# B293A_Connectors.net
KiCad netlist of a schematic drawn in Altium Designer
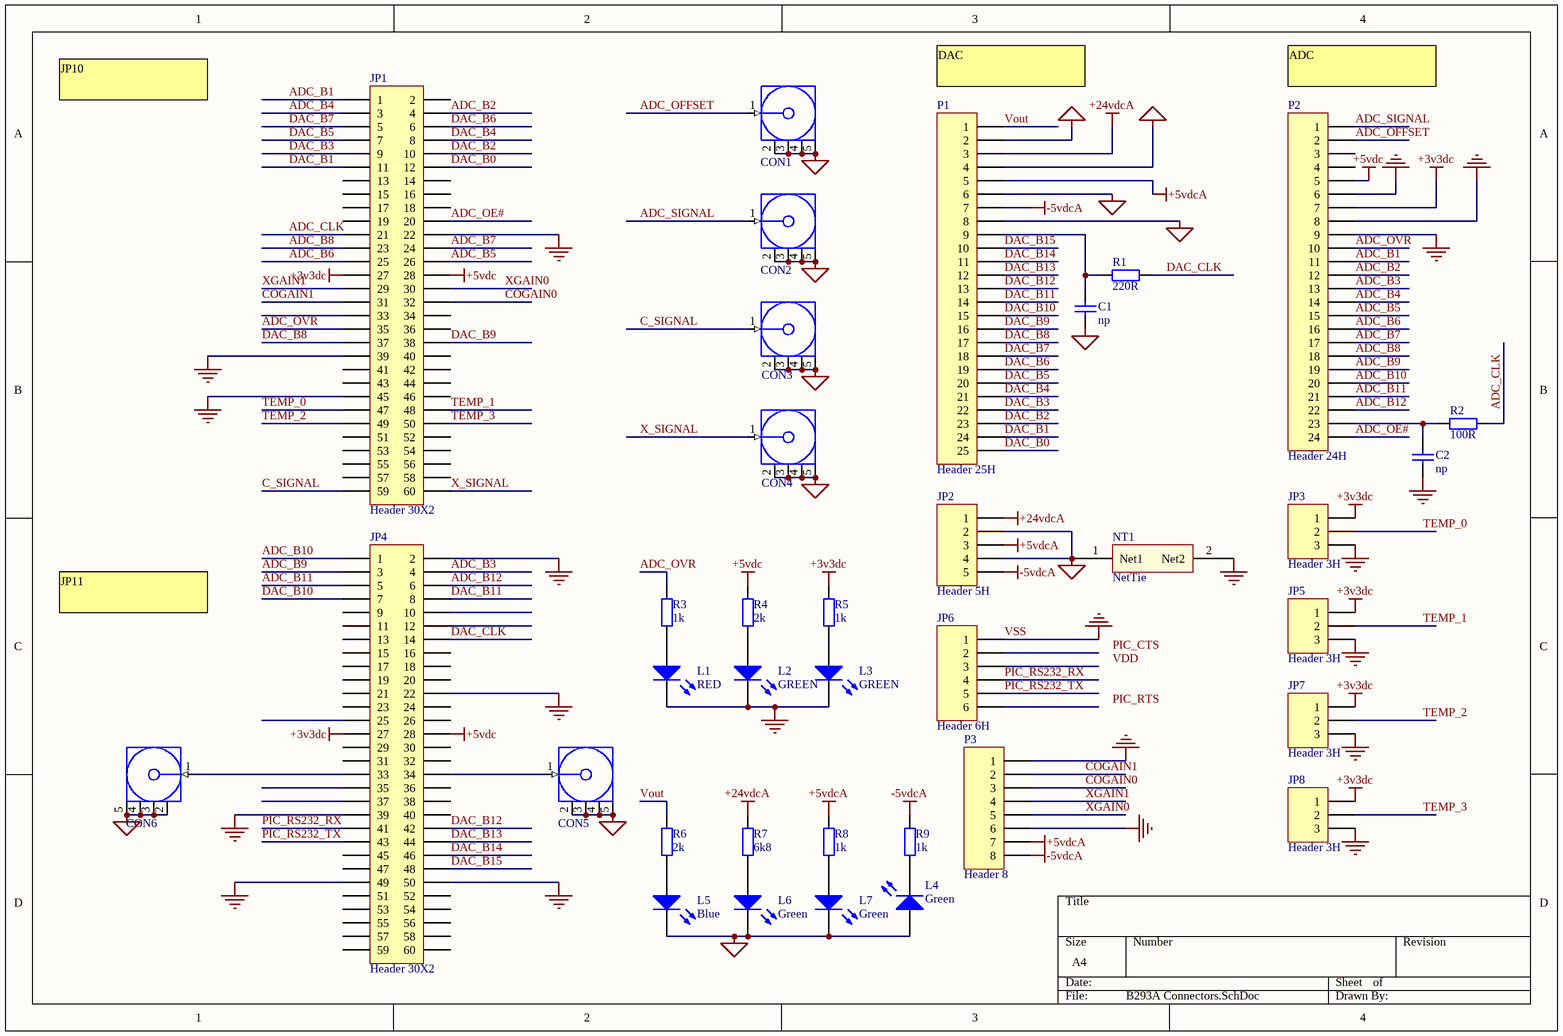
[diagram p0: B293A Connectors.SchDoc]

(export (version "E")
  (design (tool "Eeschema 10.0.6"))
  (components
    (comp (ref "C1")
      (value "np")
      (footprint "1206")
      (description "Capacitor")
      (libsource (lib "Matt SCH Library") (part "CAP"))
    )
    (comp (ref "C2")
      (value "np")
      (footprint "1206")
      (description "Capacitor")
      (libsource (lib "Matt SCH Library") (part "CAP"))
    )
    (comp (ref "CON1")
      (value "SMA Vertical")
      (footprint "Matt PCB Library:SMA Vertical")
      (fields (field (name "MANUFACTURERS PART NO") "5-1814832-1"))
      (libsource (lib "Matt SCH Library") (part "SMA Vertical"))
    )
    (comp (ref "CON2")
      (value "SMA Vertical")
      (footprint "Matt PCB Library:SMA Vertical")
      (fields (field (name "MANUFACTURERS PART NO") "5-1814832-1"))
      (libsource (lib "Matt SCH Library") (part "SMA Vertical"))
    )
    (comp (ref "CON3")
      (value "SMA Vertical")
      (footprint "Matt PCB Library:SMA Vertical")
      (fields (field (name "MANUFACTURERS PART NO") "5-1814832-1"))
      (libsource (lib "Matt SCH Library") (part "SMA Vertical"))
    )
    (comp (ref "CON4")
      (value "SMA Vertical")
      (footprint "Matt PCB Library:SMA Vertical")
      (fields (field (name "MANUFACTURERS PART NO") "5-1814832-1"))
      (libsource (lib "Matt SCH Library") (part "SMA Vertical"))
    )
    (comp (ref "CON5")
      (value "SMA Vertical")
      (footprint "Matt PCB Library:SMA Vertical")
      (fields (field (name "MANUFACTURERS PART NO") "5-1814832-1"))
      (libsource (lib "Matt SCH Library") (part "SMA Vertical"))
    )
    (comp (ref "CON6")
      (value "SMA Vertical")
      (footprint "Matt PCB Library:SMA Vertical")
      (fields (field (name "MANUFACTURERS PART NO") "5-1814832-1"))
      (libsource (lib "Matt SCH Library") (part "SMA Vertical"))
    )
    (comp (ref "JP1")
      (value "Header 30X2")
      (footprint "HDR2X30")
      (description "Header, 30-Pin, Dual row")
      (fields (field (name "PUBLISHER") "Altium Limited"))
      (libsource (lib "Miscellaneous Connectors") (part "Header 30X2"))
    )
    (comp (ref "JP2")
      (value "Header 5H")
      (footprint "HDR1X5H")
      (description "Header, 5-Pin, Right Angle")
      (fields
        (field (name "MANUFACTURER PART NUMBER") "70543-0007")
        (field (name "PUBLISHER") "Altium Limited")
      )
      (libsource (lib "Miscellaneous Connectors") (part "Header 5H"))
    )
    (comp (ref "JP3")
      (value "Header 3H")
      (footprint "HDR1X3H")
      (description "Header, 3-Pin, Right Angle")
      (fields
        (field (name "MANUFACTURER PART NUMBER") "70553-0002")
        (field (name "PUBLISHER") "Altium Limited")
      )
      (libsource (lib "Miscellaneous Connectors") (part "Header 3H"))
    )
    (comp (ref "JP4")
      (value "Header 30X2")
      (footprint "HDR2X30")
      (description "Header, 30-Pin, Dual row")
      (fields (field (name "PUBLISHER") "Altium Limited"))
      (libsource (lib "Miscellaneous Connectors") (part "Header 30X2"))
    )
    (comp (ref "JP5")
      (value "Header 3H")
      (footprint "HDR1X3H")
      (description "Header, 3-Pin, Right Angle")
      (fields (field (name "PUBLISHER") "Altium Limited"))
      (libsource (lib "Miscellaneous Connectors") (part "Header 3H"))
    )
    (comp (ref "JP6")
      (value "Header 6H")
      (footprint "HDR1X6H")
      (description "Header, 6-Pin, Right Angle")
      (fields (field (name "PUBLISHER") "Altium Limited"))
      (libsource (lib "Miscellaneous Connectors") (part "Header 6H"))
    )
    (comp (ref "JP7")
      (value "Header 3H")
      (footprint "HDR1X3H")
      (description "Header, 3-Pin, Right Angle")
      (fields (field (name "PUBLISHER") "Altium Limited"))
      (libsource (lib "Miscellaneous Connectors") (part "Header 3H"))
    )
    (comp (ref "JP8")
      (value "Header 3H")
      (footprint "HDR1X3H")
      (description "Header, 3-Pin, Right Angle")
      (fields (field (name "PUBLISHER") "Altium Limited"))
      (libsource (lib "Miscellaneous Connectors") (part "Header 3H"))
    )
    (comp (ref "L1")
      (value "RED")
      (footprint "Matt PCB Library:1206 - LED")
      (libsource (lib "Matt SCH Library") (part "LED 1206"))
    )
    (comp (ref "L2")
      (value "GREEN")
      (footprint "Matt PCB Library:1206 - LED")
      (libsource (lib "Matt SCH Library") (part "LED 1206"))
    )
    (comp (ref "L3")
      (value "GREEN")
      (footprint "Matt PCB Library:1206 - LED")
      (libsource (lib "Matt SCH Library") (part "LED 1206"))
    )
    (comp (ref "L4")
      (value "Green")
      (footprint "Matt PCB Library:1206 - LED")
      (libsource (lib "Matt SCH Library") (part "LED 1206"))
    )
    (comp (ref "L5")
      (value "Blue")
      (footprint "Matt PCB Library:1206 - LED")
      (libsource (lib "Matt SCH Library") (part "LED 1206"))
    )
    (comp (ref "L6")
      (value "Green")
      (footprint "Matt PCB Library:1206 - LED")
      (libsource (lib "Matt SCH Library") (part "LED 1206"))
    )
    (comp (ref "L7")
      (value "Green")
      (footprint "Matt PCB Library:1206 - LED")
      (libsource (lib "Matt SCH Library") (part "LED 1206"))
    )
    (comp (ref "NT1")
      (value "NetTie")
      (footprint "NetTie")
      (libsource (lib "Matt SCH Library") (part "NetTie"))
    )
    (comp (ref "P1")
      (value "Header 25H")
      (footprint "HDR1X25H")
      (description "Header, 25-Pin, Right Angle")
      (fields (field (name "PUBLISHER") "Altium Limited"))
      (libsource (lib "Miscellaneous Connectors") (part "Header 25H"))
    )
    (comp (ref "P2")
      (value "Header 24H")
      (footprint "HDR1X24H")
      (description "Header, 24-Pin, Right Angle")
      (fields (field (name "PUBLISHER") "Altium Limited"))
      (libsource (lib "Miscellaneous Connectors") (part "Header 24H"))
    )
    (comp (ref "P3")
      (value "Header 8")
      (footprint "HDR1X8")
      (description "Header, 8-Pin")
      (fields
        (field (name "MAANUFACTURER PART NUMBER") "70543-0007")
        (field (name "PUBLISHER") "Altium Limited")
      )
      (libsource (lib "Miscellaneous Connectors") (part "Header 8"))
    )
    (comp (ref "R1") (value "220R") (footprint "1206") (libsource (lib "") (part "RES2_1")))
    (comp (ref "R2") (value "100R") (footprint "1206") (libsource (lib "") (part "RES2_1")))
    (comp (ref "R3") (value "1k") (footprint "1206") (libsource (lib "Matt SCH Library") (part "RES2")))
    (comp (ref "R4") (value "2k") (footprint "1206") (libsource (lib "Matt SCH Library") (part "RES2")))
    (comp (ref "R5") (value "1k") (footprint "1206") (libsource (lib "Matt SCH Library") (part "RES2")))
    (comp (ref "R6") (value "2k") (footprint "1206") (libsource (lib "Matt SCH Library") (part "RES2")))
    (comp (ref "R7") (value "6k8") (footprint "1206") (libsource (lib "Matt SCH Library") (part "RES2")))
    (comp (ref "R8") (value "1k") (footprint "1206") (libsource (lib "Matt SCH Library") (part "RES2")))
    (comp (ref "R9") (value "1k") (footprint "1206") (libsource (lib "") (part "RES2_2")))
  )
  (nets
    (net (code "1") (name "+3v3dc") (class "Default")
      (node (ref "JP1") (pin "27") (pinfunction "27_27") (pintype "passive"))
      (node (ref "JP3") (pin "1") (pinfunction "1_1") (pintype "passive"))
      (node (ref "JP4") (pin "27") (pinfunction "27_27") (pintype "passive"))
      (node (ref "JP5") (pin "1") (pinfunction "1_1") (pintype "passive"))
      (node (ref "JP7") (pin "1") (pinfunction "1_1") (pintype "passive"))
      (node (ref "JP8") (pin "1") (pinfunction "1_1") (pintype "passive"))
      (node (ref "P2") (pin "7") (pinfunction "7_7") (pintype "passive"))
      (node (ref "R5") (pin "2") (pinfunction "2_2") (pintype "passive"))
    )
    (net (code "2") (name "+5vdc") (class "Default")
      (node (ref "JP1") (pin "28") (pinfunction "28_28") (pintype "passive"))
      (node (ref "JP4") (pin "28") (pinfunction "28_28") (pintype "passive"))
      (node (ref "P2") (pin "5") (pinfunction "5_5") (pintype "passive"))
      (node (ref "R4") (pin "2") (pinfunction "2_2") (pintype "passive"))
    )
    (net (code "3") (name "+5vdcA") (class "Default")
      (node (ref "JP2") (pin "3") (pinfunction "3_3") (pintype "passive"))
      (node (ref "P1") (pin "5") (pinfunction "5_5") (pintype "passive"))
      (node (ref "P3") (pin "7") (pinfunction "7_7") (pintype "passive"))
      (node (ref "R8") (pin "2") (pinfunction "2_2") (pintype "passive"))
    )
    (net (code "4") (name "+24vdcA") (class "Default")
      (node (ref "JP2") (pin "1") (pinfunction "1_1") (pintype "passive"))
      (node (ref "P1") (pin "3") (pinfunction "3_3") (pintype "passive"))
      (node (ref "R7") (pin "2") (pinfunction "2_2") (pintype "passive"))
    )
    (net (code "5") (name "-5vdcA") (class "Default")
      (node (ref "JP2") (pin "5") (pinfunction "5_5") (pintype "passive"))
      (node (ref "P1") (pin "7") (pinfunction "7_7") (pintype "passive"))
      (node (ref "P3") (pin "8") (pinfunction "8_8") (pintype "passive"))
      (node (ref "R9") (pin "1") (pinfunction "1_1") (pintype "passive"))
    )
    (net (code "6") (name "/ADC_B1") (class "Default")
      (node (ref "JP1") (pin "1") (pinfunction "1_1") (pintype "passive"))
      (node (ref "P2") (pin "11") (pinfunction "11_11") (pintype "passive"))
    )
    (net (code "7") (name "/ADC_B2") (class "Default")
      (node (ref "JP1") (pin "4") (pinfunction "4_4") (pintype "passive"))
      (node (ref "P2") (pin "12") (pinfunction "12_12") (pintype "passive"))
    )
    (net (code "8") (name "/ADC_B3") (class "Default")
      (node (ref "JP4") (pin "4") (pinfunction "4_4") (pintype "passive"))
      (node (ref "P2") (pin "13") (pinfunction "13_13") (pintype "passive"))
    )
    (net (code "9") (name "/ADC_B4") (class "Default")
      (node (ref "JP1") (pin "3") (pinfunction "3_3") (pintype "passive"))
      (node (ref "P2") (pin "14") (pinfunction "14_14") (pintype "passive"))
    )
    (net (code "10") (name "/ADC_B5") (class "Default")
      (node (ref "JP1") (pin "26") (pinfunction "26_26") (pintype "passive"))
      (node (ref "P2") (pin "15") (pinfunction "15_15") (pintype "passive"))
    )
    (net (code "11") (name "/ADC_B6") (class "Default")
      (node (ref "JP1") (pin "25") (pinfunction "25_25") (pintype "passive"))
      (node (ref "P2") (pin "16") (pinfunction "16_16") (pintype "passive"))
    )
    (net (code "12") (name "/ADC_B7") (class "Default")
      (node (ref "JP1") (pin "24") (pinfunction "24_24") (pintype "passive"))
      (node (ref "P2") (pin "17") (pinfunction "17_17") (pintype "passive"))
    )
    (net (code "13") (name "/ADC_B8") (class "Default")
      (node (ref "JP1") (pin "23") (pinfunction "23_23") (pintype "passive"))
      (node (ref "P2") (pin "18") (pinfunction "18_18") (pintype "passive"))
    )
    (net (code "14") (name "/ADC_B9") (class "Default")
      (node (ref "JP4") (pin "3") (pinfunction "3_3") (pintype "passive"))
      (node (ref "P2") (pin "19") (pinfunction "19_19") (pintype "passive"))
    )
    (net (code "15") (name "/ADC_B10") (class "Default")
      (node (ref "JP4") (pin "1") (pinfunction "1_1") (pintype "passive"))
      (node (ref "P2") (pin "20") (pinfunction "20_20") (pintype "passive"))
    )
    (net (code "16") (name "/ADC_B11") (class "Default")
      (node (ref "JP4") (pin "5") (pinfunction "5_5") (pintype "passive"))
      (node (ref "P2") (pin "21") (pinfunction "21_21") (pintype "passive"))
    )
    (net (code "17") (name "/ADC_B12") (class "Default")
      (node (ref "JP4") (pin "6") (pinfunction "6_6") (pintype "passive"))
      (node (ref "P2") (pin "22") (pinfunction "22_22") (pintype "passive"))
    )
    (net (code "18") (name "/ADC_CLK") (class "Default")
      (node (ref "JP1") (pin "21") (pinfunction "21_21") (pintype "passive"))
      (node (ref "R2") (pin "2") (pinfunction "2_2") (pintype "passive"))
    )
    (net (code "19") (name "/ADC_OE#") (class "Default")
      (node (ref "JP1") (pin "20") (pinfunction "20_20") (pintype "passive"))
      (node (ref "P2") (pin "24") (pinfunction "24_24") (pintype "passive"))
    )
    (net (code "20") (name "/ADC_OFFSET") (class "Default")
      (node (ref "CON1") (pin "1") (pinfunction "Signal_1") (pintype "input"))
      (node (ref "P2") (pin "2") (pinfunction "2_2") (pintype "passive"))
    )
    (net (code "21") (name "/ADC_OVR") (class "Default")
      (node (ref "JP1") (pin "35") (pinfunction "35_35") (pintype "passive"))
      (node (ref "P2") (pin "10") (pinfunction "10_10") (pintype "passive"))
      (node (ref "R3") (pin "2") (pinfunction "2_2") (pintype "passive"))
    )
    (net (code "22") (name "/ADC_SIGNAL") (class "Default")
      (node (ref "CON2") (pin "1") (pinfunction "Signal_1") (pintype "input"))
      (node (ref "P2") (pin "1") (pinfunction "1_1") (pintype "passive"))
    )
    (net (code "23") (name "/COGAIN0") (class "Default")
      (node (ref "JP1") (pin "32") (pinfunction "32_32") (pintype "passive"))
      (node (ref "P3") (pin "3") (pinfunction "3_3") (pintype "passive"))
    )
    (net (code "24") (name "/COGAIN1") (class "Default")
      (node (ref "JP1") (pin "31") (pinfunction "31_31") (pintype "passive"))
      (node (ref "P3") (pin "2") (pinfunction "2_2") (pintype "passive"))
    )
    (net (code "25") (name "/C_SIGNAL") (class "Default")
      (node (ref "CON3") (pin "1") (pinfunction "Signal_1") (pintype "input"))
      (node (ref "JP1") (pin "59") (pinfunction "59_59") (pintype "passive"))
    )
    (net (code "26") (name "/DAC_B0") (class "Default")
      (node (ref "JP1") (pin "12") (pinfunction "12_12") (pintype "passive"))
      (node (ref "P1") (pin "25") (pinfunction "25_25") (pintype "passive"))
    )
    (net (code "27") (name "/DAC_B1") (class "Default")
      (node (ref "JP1") (pin "11") (pinfunction "11_11") (pintype "passive"))
      (node (ref "P1") (pin "24") (pinfunction "24_24") (pintype "passive"))
    )
    (net (code "28") (name "/DAC_B2") (class "Default")
      (node (ref "JP1") (pin "10") (pinfunction "10_10") (pintype "passive"))
      (node (ref "P1") (pin "23") (pinfunction "23_23") (pintype "passive"))
    )
    (net (code "29") (name "/DAC_B3") (class "Default")
      (node (ref "JP1") (pin "9") (pinfunction "9_9") (pintype "passive"))
      (node (ref "P1") (pin "22") (pinfunction "22_22") (pintype "passive"))
    )
    (net (code "30") (name "/DAC_B4") (class "Default")
      (node (ref "JP1") (pin "8") (pinfunction "8_8") (pintype "passive"))
      (node (ref "P1") (pin "21") (pinfunction "21_21") (pintype "passive"))
    )
    (net (code "31") (name "/DAC_B5") (class "Default")
      (node (ref "JP1") (pin "7") (pinfunction "7_7") (pintype "passive"))
      (node (ref "P1") (pin "20") (pinfunction "20_20") (pintype "passive"))
    )
    (net (code "32") (name "/DAC_B6") (class "Default")
      (node (ref "JP1") (pin "6") (pinfunction "6_6") (pintype "passive"))
      (node (ref "P1") (pin "19") (pinfunction "19_19") (pintype "passive"))
    )
    (net (code "33") (name "/DAC_B7") (class "Default")
      (node (ref "JP1") (pin "5") (pinfunction "5_5") (pintype "passive"))
      (node (ref "P1") (pin "18") (pinfunction "18_18") (pintype "passive"))
    )
    (net (code "34") (name "/DAC_B8") (class "Default")
      (node (ref "JP1") (pin "37") (pinfunction "37_37") (pintype "passive"))
      (node (ref "P1") (pin "17") (pinfunction "17_17") (pintype "passive"))
    )
    (net (code "35") (name "/DAC_B9") (class "Default")
      (node (ref "JP1") (pin "38") (pinfunction "38_38") (pintype "passive"))
      (node (ref "P1") (pin "16") (pinfunction "16_16") (pintype "passive"))
    )
    (net (code "36") (name "/DAC_B10") (class "Default")
      (node (ref "JP4") (pin "7") (pinfunction "7_7") (pintype "passive"))
      (node (ref "P1") (pin "15") (pinfunction "15_15") (pintype "passive"))
    )
    (net (code "37") (name "/DAC_B11") (class "Default")
      (node (ref "JP4") (pin "8") (pinfunction "8_8") (pintype "passive"))
      (node (ref "P1") (pin "14") (pinfunction "14_14") (pintype "passive"))
    )
    (net (code "38") (name "/DAC_B12") (class "Default")
      (node (ref "JP4") (pin "42") (pinfunction "42_42") (pintype "passive"))
      (node (ref "P1") (pin "13") (pinfunction "13_13") (pintype "passive"))
    )
    (net (code "39") (name "/DAC_B13") (class "Default")
      (node (ref "JP4") (pin "44") (pinfunction "44_44") (pintype "passive"))
      (node (ref "P1") (pin "12") (pinfunction "12_12") (pintype "passive"))
    )
    (net (code "40") (name "/DAC_B14") (class "Default")
      (node (ref "JP4") (pin "46") (pinfunction "46_46") (pintype "passive"))
      (node (ref "P1") (pin "11") (pinfunction "11_11") (pintype "passive"))
    )
    (net (code "41") (name "/DAC_B15") (class "Default")
      (node (ref "JP4") (pin "48") (pinfunction "48_48") (pintype "passive"))
      (node (ref "P1") (pin "10") (pinfunction "10_10") (pintype "passive"))
    )
    (net (code "42") (name "/DAC_CLK") (class "Default")
      (node (ref "JP4") (pin "14") (pinfunction "14_14") (pintype "passive"))
      (node (ref "R1") (pin "2") (pinfunction "2_2") (pintype "passive"))
    )
    (net (code "44") (name "/PIC_RS232_RX") (class "Default")
      (node (ref "JP4") (pin "41") (pinfunction "41_41") (pintype "passive"))
      (node (ref "JP6") (pin "4") (pinfunction "4_4") (pintype "passive"))
    )
    (net (code "45") (name "/PIC_RS232_TX") (class "Default")
      (node (ref "JP4") (pin "43") (pinfunction "43_43") (pintype "passive"))
      (node (ref "JP6") (pin "5") (pinfunction "5_5") (pintype "passive"))
    )
    (net (code "47") (name "/TEMP_0") (class "Default")
      (node (ref "JP1") (pin "47") (pinfunction "47_47") (pintype "passive"))
      (node (ref "JP3") (pin "2") (pinfunction "2_2") (pintype "passive"))
    )
    (net (code "48") (name "/TEMP_1") (class "Default")
      (node (ref "JP1") (pin "48") (pinfunction "48_48") (pintype "passive"))
      (node (ref "JP5") (pin "2") (pinfunction "2_2") (pintype "passive"))
    )
    (net (code "49") (name "/TEMP_2") (class "Default")
      (node (ref "JP1") (pin "49") (pinfunction "49_49") (pintype "passive"))
      (node (ref "JP7") (pin "2") (pinfunction "2_2") (pintype "passive"))
    )
    (net (code "50") (name "/TEMP_3") (class "Default")
      (node (ref "JP1") (pin "50") (pinfunction "50_50") (pintype "passive"))
      (node (ref "JP8") (pin "2") (pinfunction "2_2") (pintype "passive"))
    )
    (net (code "52") (name "/Vout") (class "Default")
      (node (ref "P1") (pin "1") (pinfunction "1_1") (pintype "passive"))
      (node (ref "R6") (pin "2") (pinfunction "2_2") (pintype "passive"))
    )
    (net (code "53") (name "/XGAIN0") (class "Default")
      (node (ref "JP1") (pin "30") (pinfunction "30_30") (pintype "passive"))
      (node (ref "P3") (pin "5") (pinfunction "5_5") (pintype "passive"))
    )
    (net (code "54") (name "/XGAIN1") (class "Default")
      (node (ref "JP1") (pin "29") (pinfunction "29_29") (pintype "passive"))
      (node (ref "P3") (pin "4") (pinfunction "4_4") (pintype "passive"))
    )
    (net (code "55") (name "/X_SIGNAL") (class "Default")
      (node (ref "CON4") (pin "1") (pinfunction "Signal_1") (pintype "input"))
      (node (ref "JP1") (pin "60") (pinfunction "60_60") (pintype "passive"))
    )
    (net (code "56") (name "AGND") (class "Default")
      (node (ref "C1") (pin "2") (pinfunction "2_2") (pintype "passive"))
      (node (ref "CON1") (pin "2") (pinfunction "GND_2") (pintype "power_in"))
      (node (ref "CON1") (pin "3") (pinfunction "GND_3") (pintype "power_in"))
      (node (ref "CON1") (pin "4") (pinfunction "GND_4") (pintype "power_in"))
      (node (ref "CON1") (pin "5") (pinfunction "GND_5") (pintype "power_in"))
      (node (ref "CON2") (pin "2") (pinfunction "GND_2") (pintype "power_in"))
      (node (ref "CON2") (pin "3") (pinfunction "GND_3") (pintype "power_in"))
      (node (ref "CON2") (pin "4") (pinfunction "GND_4") (pintype "power_in"))
      (node (ref "CON2") (pin "5") (pinfunction "GND_5") (pintype "power_in"))
      (node (ref "CON3") (pin "2") (pinfunction "GND_2") (pintype "power_in"))
      (node (ref "CON3") (pin "3") (pinfunction "GND_3") (pintype "power_in"))
      (node (ref "CON3") (pin "4") (pinfunction "GND_4") (pintype "power_in"))
      (node (ref "CON3") (pin "5") (pinfunction "GND_5") (pintype "power_in"))
      (node (ref "CON4") (pin "2") (pinfunction "GND_2") (pintype "power_in"))
      (node (ref "CON4") (pin "3") (pinfunction "GND_3") (pintype "power_in"))
      (node (ref "CON4") (pin "4") (pinfunction "GND_4") (pintype "power_in"))
      (node (ref "CON4") (pin "5") (pinfunction "GND_5") (pintype "power_in"))
      (node (ref "CON5") (pin "2") (pinfunction "GND_2") (pintype "power_in"))
      (node (ref "CON5") (pin "3") (pinfunction "GND_3") (pintype "power_in"))
      (node (ref "CON5") (pin "4") (pinfunction "GND_4") (pintype "power_in"))
      (node (ref "CON5") (pin "5") (pinfunction "GND_5") (pintype "power_in"))
      (node (ref "CON6") (pin "2") (pinfunction "GND_2") (pintype "power_in"))
      (node (ref "CON6") (pin "3") (pinfunction "GND_3") (pintype "power_in"))
      (node (ref "CON6") (pin "4") (pinfunction "GND_4") (pintype "power_in"))
      (node (ref "CON6") (pin "5") (pinfunction "GND_5") (pintype "power_in"))
      (node (ref "JP2") (pin "2") (pinfunction "2_2") (pintype "passive"))
      (node (ref "JP2") (pin "4") (pinfunction "4_4") (pintype "passive"))
      (node (ref "L4") (pin "A") (pinfunction "A_A") (pintype "passive"))
      (node (ref "L5") (pin "K") (pinfunction "K_K") (pintype "passive"))
      (node (ref "L6") (pin "K") (pinfunction "K_K") (pintype "passive"))
      (node (ref "L7") (pin "K") (pinfunction "K_K") (pintype "passive"))
      (node (ref "NT1") (pin "1") (pinfunction "Net1_1") (pintype "passive"))
      (node (ref "P1") (pin "2") (pinfunction "2_2") (pintype "passive"))
      (node (ref "P1") (pin "4") (pinfunction "4_4") (pintype "passive"))
      (node (ref "P1") (pin "6") (pinfunction "6_6") (pintype "passive"))
      (node (ref "P1") (pin "8") (pinfunction "8_8") (pintype "passive"))
    )
    (net (code "57") (name "GND") (class "Default")
      (node (ref "C2") (pin "2") (pinfunction "2_2") (pintype "passive"))
      (node (ref "JP1") (pin "22") (pinfunction "22_22") (pintype "passive"))
      (node (ref "JP1") (pin "39") (pinfunction "39_39") (pintype "passive"))
      (node (ref "JP1") (pin "45") (pinfunction "45_45") (pintype "passive"))
      (node (ref "JP3") (pin "3") (pinfunction "3_3") (pintype "passive"))
      (node (ref "JP4") (pin "2") (pinfunction "2_2") (pintype "passive"))
      (node (ref "JP4") (pin "22") (pinfunction "22_22") (pintype "passive"))
      (node (ref "JP4") (pin "39") (pinfunction "39_39") (pintype "passive"))
      (node (ref "JP4") (pin "49") (pinfunction "49_49") (pintype "passive"))
      (node (ref "JP4") (pin "50") (pinfunction "50_50") (pintype "passive"))
      (node (ref "JP5") (pin "3") (pinfunction "3_3") (pintype "passive"))
      (node (ref "JP6") (pin "1") (pinfunction "1_1") (pintype "passive"))
      (node (ref "JP7") (pin "3") (pinfunction "3_3") (pintype "passive"))
      (node (ref "JP8") (pin "3") (pinfunction "3_3") (pintype "passive"))
      (node (ref "L1") (pin "K") (pinfunction "K_K") (pintype "passive"))
      (node (ref "L2") (pin "K") (pinfunction "K_K") (pintype "passive"))
      (node (ref "L3") (pin "K") (pinfunction "K_K") (pintype "passive"))
      (node (ref "NT1") (pin "2") (pinfunction "Net2_2") (pintype "passive"))
      (node (ref "P2") (pin "6") (pinfunction "6_6") (pintype "passive"))
      (node (ref "P2") (pin "8") (pinfunction "8_8") (pintype "passive"))
      (node (ref "P2") (pin "9") (pinfunction "9_9") (pintype "passive"))
      (node (ref "P3") (pin "1") (pinfunction "1_1") (pintype "passive"))
      (node (ref "P3") (pin "6") (pinfunction "6_6") (pintype "passive"))
    )
    (net (code "58") (name "Net-(C1-Pad1)") (class "Default")
      (node (ref "C1") (pin "1") (pinfunction "1_1") (pintype "passive"))
      (node (ref "P1") (pin "9") (pinfunction "9_9") (pintype "passive"))
      (node (ref "R1") (pin "1") (pinfunction "1_1") (pintype "passive"))
    )
    (net (code "59") (name "Net-(C2-Pad1)") (class "Default")
      (node (ref "C2") (pin "1") (pinfunction "1_1") (pintype "passive"))
      (node (ref "P2") (pin "23") (pinfunction "23_23") (pintype "passive"))
      (node (ref "R2") (pin "1") (pinfunction "1_1") (pintype "passive"))
    )
    (net (code "60") (name "Net-(CON5-Signal)") (class "Default")
      (node (ref "CON5") (pin "1") (pinfunction "Signal_1") (pintype "input"))
      (node (ref "JP4") (pin "34") (pinfunction "34_34") (pintype "passive"))
    )
    (net (code "61") (name "Net-(CON6-Signal)") (class "Default")
      (node (ref "CON6") (pin "1") (pinfunction "Signal_1") (pintype "input"))
      (node (ref "JP4") (pin "33") (pinfunction "33_33") (pintype "passive"))
    )
    (net (code "62") (name "Net-(L1-PadA)") (class "Default")
      (node (ref "L1") (pin "A") (pinfunction "A_A") (pintype "passive"))
      (node (ref "R3") (pin "1") (pinfunction "1_1") (pintype "passive"))
    )
    (net (code "63") (name "Net-(L2-PadA)") (class "Default")
      (node (ref "L2") (pin "A") (pinfunction "A_A") (pintype "passive"))
      (node (ref "R4") (pin "1") (pinfunction "1_1") (pintype "passive"))
    )
    (net (code "64") (name "Net-(L3-PadA)") (class "Default")
      (node (ref "L3") (pin "A") (pinfunction "A_A") (pintype "passive"))
      (node (ref "R5") (pin "1") (pinfunction "1_1") (pintype "passive"))
    )
    (net (code "65") (name "Net-(L4-PadK)") (class "Default")
      (node (ref "L4") (pin "K") (pinfunction "K_K") (pintype "passive"))
      (node (ref "R9") (pin "2") (pinfunction "2_2") (pintype "passive"))
    )
    (net (code "66") (name "Net-(L5-PadA)") (class "Default")
      (node (ref "L5") (pin "A") (pinfunction "A_A") (pintype "passive"))
      (node (ref "R6") (pin "1") (pinfunction "1_1") (pintype "passive"))
    )
    (net (code "67") (name "Net-(L6-PadA)") (class "Default")
      (node (ref "L6") (pin "A") (pinfunction "A_A") (pintype "passive"))
      (node (ref "R7") (pin "1") (pinfunction "1_1") (pintype "passive"))
    )
    (net (code "68") (name "Net-(L7-PadA)") (class "Default")
      (node (ref "L7") (pin "A") (pinfunction "A_A") (pintype "passive"))
      (node (ref "R8") (pin "1") (pinfunction "1_1") (pintype "passive"))
    )
    (net (code "69") (name "unconnected-(JP1-Pad2)") (class "Default")
      (node (ref "JP1") (pin "2") (pinfunction "2_2") (pintype "passive"))
    )
    (net (code "70") (name "unconnected-(JP1-Pad13)") (class "Default")
      (node (ref "JP1") (pin "13") (pinfunction "13_13") (pintype "passive"))
    )
    (net (code "71") (name "unconnected-(JP1-Pad14)") (class "Default")
      (node (ref "JP1") (pin "14") (pinfunction "14_14") (pintype "passive"))
    )
    (net (code "72") (name "unconnected-(JP1-Pad15)") (class "Default")
      (node (ref "JP1") (pin "15") (pinfunction "15_15") (pintype "passive"))
    )
    (net (code "73") (name "unconnected-(JP1-Pad16)") (class "Default")
      (node (ref "JP1") (pin "16") (pinfunction "16_16") (pintype "passive"))
    )
    (net (code "74") (name "unconnected-(JP1-Pad17)") (class "Default")
      (node (ref "JP1") (pin "17") (pinfunction "17_17") (pintype "passive"))
    )
    (net (code "75") (name "unconnected-(JP1-Pad18)") (class "Default")
      (node (ref "JP1") (pin "18") (pinfunction "18_18") (pintype "passive"))
    )
    (net (code "76") (name "unconnected-(JP1-Pad19)") (class "Default")
      (node (ref "JP1") (pin "19") (pinfunction "19_19") (pintype "passive"))
    )
    (net (code "77") (name "unconnected-(JP1-Pad33)") (class "Default")
      (node (ref "JP1") (pin "33") (pinfunction "33_33") (pintype "passive"))
    )
    (net (code "78") (name "unconnected-(JP1-Pad34)") (class "Default")
      (node (ref "JP1") (pin "34") (pinfunction "34_34") (pintype "passive"))
    )
    (net (code "79") (name "unconnected-(JP1-Pad36)") (class "Default")
      (node (ref "JP1") (pin "36") (pinfunction "36_36") (pintype "passive"))
    )
    (net (code "80") (name "unconnected-(JP1-Pad40)") (class "Default")
      (node (ref "JP1") (pin "40") (pinfunction "40_40") (pintype "passive"))
    )
    (net (code "81") (name "unconnected-(JP1-Pad41)") (class "Default")
      (node (ref "JP1") (pin "41") (pinfunction "41_41") (pintype "passive"))
    )
    (net (code "82") (name "unconnected-(JP1-Pad42)") (class "Default")
      (node (ref "JP1") (pin "42") (pinfunction "42_42") (pintype "passive"))
    )
    (net (code "83") (name "unconnected-(JP1-Pad43)") (class "Default")
      (node (ref "JP1") (pin "43") (pinfunction "43_43") (pintype "passive"))
    )
    (net (code "84") (name "unconnected-(JP1-Pad44)") (class "Default")
      (node (ref "JP1") (pin "44") (pinfunction "44_44") (pintype "passive"))
    )
    (net (code "85") (name "unconnected-(JP1-Pad46)") (class "Default")
      (node (ref "JP1") (pin "46") (pinfunction "46_46") (pintype "passive"))
    )
    (net (code "86") (name "unconnected-(JP1-Pad51)") (class "Default")
      (node (ref "JP1") (pin "51") (pinfunction "51_51") (pintype "passive"))
    )
    (net (code "87") (name "unconnected-(JP1-Pad52)") (class "Default")
      (node (ref "JP1") (pin "52") (pinfunction "52_52") (pintype "passive"))
    )
    (net (code "88") (name "unconnected-(JP1-Pad53)") (class "Default")
      (node (ref "JP1") (pin "53") (pinfunction "53_53") (pintype "passive"))
    )
    (net (code "89") (name "unconnected-(JP1-Pad54)") (class "Default")
      (node (ref "JP1") (pin "54") (pinfunction "54_54") (pintype "passive"))
    )
    (net (code "90") (name "unconnected-(JP1-Pad55)") (class "Default")
      (node (ref "JP1") (pin "55") (pinfunction "55_55") (pintype "passive"))
    )
    (net (code "91") (name "unconnected-(JP1-Pad56)") (class "Default")
      (node (ref "JP1") (pin "56") (pinfunction "56_56") (pintype "passive"))
    )
    (net (code "92") (name "unconnected-(JP1-Pad57)") (class "Default")
      (node (ref "JP1") (pin "57") (pinfunction "57_57") (pintype "passive"))
    )
    (net (code "93") (name "unconnected-(JP1-Pad58)") (class "Default")
      (node (ref "JP1") (pin "58") (pinfunction "58_58") (pintype "passive"))
    )
    (net (code "94") (name "unconnected-(JP4-Pad9)") (class "Default")
      (node (ref "JP4") (pin "9") (pinfunction "9_9") (pintype "passive"))
    )
    (net (code "95") (name "unconnected-(JP4-Pad10)") (class "Default")
      (node (ref "JP4") (pin "10") (pinfunction "10_10") (pintype "passive"))
    )
    (net (code "96") (name "unconnected-(JP4-Pad11)") (class "Default")
      (node (ref "JP4") (pin "11") (pinfunction "11_11") (pintype "passive"))
    )
    (net (code "97") (name "unconnected-(JP4-Pad12)") (class "Default")
      (node (ref "JP4") (pin "12") (pinfunction "12_12") (pintype "passive"))
    )
    (net (code "98") (name "unconnected-(JP4-Pad13)") (class "Default")
      (node (ref "JP4") (pin "13") (pinfunction "13_13") (pintype "passive"))
    )
    (net (code "99") (name "unconnected-(JP4-Pad15)") (class "Default")
      (node (ref "JP4") (pin "15") (pinfunction "15_15") (pintype "passive"))
    )
    (net (code "100") (name "unconnected-(JP4-Pad16)") (class "Default")
      (node (ref "JP4") (pin "16") (pinfunction "16_16") (pintype "passive"))
    )
    (net (code "101") (name "unconnected-(JP4-Pad17)") (class "Default")
      (node (ref "JP4") (pin "17") (pinfunction "17_17") (pintype "passive"))
    )
    (net (code "102") (name "unconnected-(JP4-Pad18)") (class "Default")
      (node (ref "JP4") (pin "18") (pinfunction "18_18") (pintype "passive"))
    )
    (net (code "103") (name "unconnected-(JP4-Pad19)") (class "Default")
      (node (ref "JP4") (pin "19") (pinfunction "19_19") (pintype "passive"))
    )
    (net (code "104") (name "unconnected-(JP4-Pad20)") (class "Default")
      (node (ref "JP4") (pin "20") (pinfunction "20_20") (pintype "passive"))
    )
    (net (code "105") (name "unconnected-(JP4-Pad21)") (class "Default")
      (node (ref "JP4") (pin "21") (pinfunction "21_21") (pintype "passive"))
    )
    (net (code "106") (name "unconnected-(JP4-Pad23)") (class "Default")
      (node (ref "JP4") (pin "23") (pinfunction "23_23") (pintype "passive"))
    )
    (net (code "107") (name "unconnected-(JP4-Pad24)") (class "Default")
      (node (ref "JP4") (pin "24") (pinfunction "24_24") (pintype "passive"))
    )
    (net (code "108") (name "unconnected-(JP4-Pad25)") (class "Default")
      (node (ref "JP4") (pin "25") (pinfunction "25_25") (pintype "passive"))
    )
    (net (code "109") (name "unconnected-(JP4-Pad26)") (class "Default")
      (node (ref "JP4") (pin "26") (pinfunction "26_26") (pintype "passive"))
    )
    (net (code "110") (name "unconnected-(JP4-Pad29)") (class "Default")
      (node (ref "JP4") (pin "29") (pinfunction "29_29") (pintype "passive"))
    )
    (net (code "111") (name "unconnected-(JP4-Pad30)") (class "Default")
      (node (ref "JP4") (pin "30") (pinfunction "30_30") (pintype "passive"))
    )
    (net (code "112") (name "unconnected-(JP4-Pad31)") (class "Default")
      (node (ref "JP4") (pin "31") (pinfunction "31_31") (pintype "passive"))
    )
    (net (code "113") (name "unconnected-(JP4-Pad32)") (class "Default")
      (node (ref "JP4") (pin "32") (pinfunction "32_32") (pintype "passive"))
    )
    (net (code "114") (name "unconnected-(JP4-Pad35)") (class "Default")
      (node (ref "JP4") (pin "35") (pinfunction "35_35") (pintype "passive"))
    )
    (net (code "115") (name "unconnected-(JP4-Pad36)") (class "Default")
      (node (ref "JP4") (pin "36") (pinfunction "36_36") (pintype "passive"))
    )
    (net (code "116") (name "unconnected-(JP4-Pad37)") (class "Default")
      (node (ref "JP4") (pin "37") (pinfunction "37_37") (pintype "passive"))
    )
    (net (code "117") (name "unconnected-(JP4-Pad38)") (class "Default")
      (node (ref "JP4") (pin "38") (pinfunction "38_38") (pintype "passive"))
    )
    (net (code "118") (name "unconnected-(JP4-Pad40)") (class "Default")
      (node (ref "JP4") (pin "40") (pinfunction "40_40") (pintype "passive"))
    )
    (net (code "119") (name "unconnected-(JP4-Pad45)") (class "Default")
      (node (ref "JP4") (pin "45") (pinfunction "45_45") (pintype "passive"))
    )
    (net (code "120") (name "unconnected-(JP4-Pad47)") (class "Default")
      (node (ref "JP4") (pin "47") (pinfunction "47_47") (pintype "passive"))
    )
    (net (code "121") (name "unconnected-(JP4-Pad51)") (class "Default")
      (node (ref "JP4") (pin "51") (pinfunction "51_51") (pintype "passive"))
    )
    (net (code "122") (name "unconnected-(JP4-Pad52)") (class "Default")
      (node (ref "JP4") (pin "52") (pinfunction "52_52") (pintype "passive"))
    )
    (net (code "123") (name "unconnected-(JP4-Pad53)") (class "Default")
      (node (ref "JP4") (pin "53") (pinfunction "53_53") (pintype "passive"))
    )
    (net (code "124") (name "unconnected-(JP4-Pad54)") (class "Default")
      (node (ref "JP4") (pin "54") (pinfunction "54_54") (pintype "passive"))
    )
    (net (code "125") (name "unconnected-(JP4-Pad55)") (class "Default")
      (node (ref "JP4") (pin "55") (pinfunction "55_55") (pintype "passive"))
    )
    (net (code "126") (name "unconnected-(JP4-Pad56)") (class "Default")
      (node (ref "JP4") (pin "56") (pinfunction "56_56") (pintype "passive"))
    )
    (net (code "127") (name "unconnected-(JP4-Pad57)") (class "Default")
      (node (ref "JP4") (pin "57") (pinfunction "57_57") (pintype "passive"))
    )
    (net (code "128") (name "unconnected-(JP4-Pad58)") (class "Default")
      (node (ref "JP4") (pin "58") (pinfunction "58_58") (pintype "passive"))
    )
    (net (code "129") (name "unconnected-(JP4-Pad59)") (class "Default")
      (node (ref "JP4") (pin "59") (pinfunction "59_59") (pintype "passive"))
    )
    (net (code "130") (name "unconnected-(JP4-Pad60)") (class "Default")
      (node (ref "JP4") (pin "60") (pinfunction "60_60") (pintype "passive"))
    )
    (net (code "131") (name "unconnected-(JP6-Pad2)") (class "Default")
      (node (ref "JP6") (pin "2") (pinfunction "2_2") (pintype "passive"))
    )
    (net (code "132") (name "unconnected-(JP6-Pad3)") (class "Default")
      (node (ref "JP6") (pin "3") (pinfunction "3_3") (pintype "passive"))
    )
    (net (code "133") (name "unconnected-(JP6-Pad6)") (class "Default")
      (node (ref "JP6") (pin "6") (pinfunction "6_6") (pintype "passive"))
    )
    (net (code "134") (name "unconnected-(P2-Pad3)") (class "Default")
      (node (ref "P2") (pin "3") (pinfunction "3_3") (pintype "passive"))
    )
    (net (code "135") (name "unconnected-(P2-Pad4)") (class "Default")
      (node (ref "P2") (pin "4") (pinfunction "4_4") (pintype "passive"))
    )
  )
)
